# ReWireShield.net
KiCad netlist of a schematic drawn in EAGLE
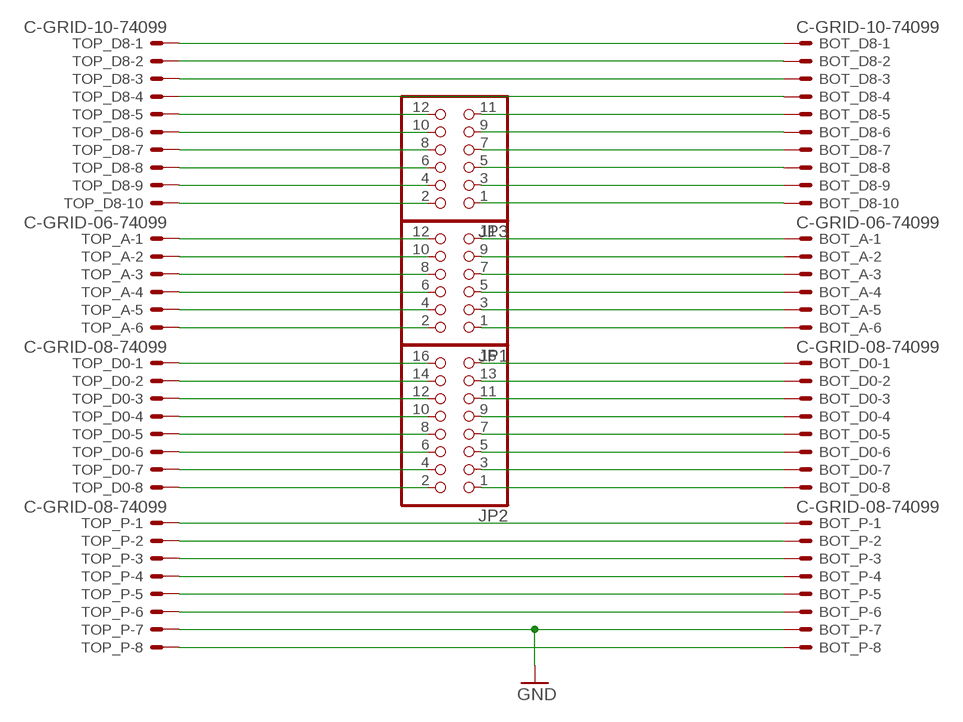
[diagram p0: schematic, sheet 1]

(export (version "E")
  (design (tool "Eeschema 10.0.6"))
  (components
    (comp (ref "BOT_A")
      (value "C-GRID-06-74099")
      (footprint "eagle-import:74099-06")
      (libsource (lib "eagle-import") (part "C-GRID-06-74099"))
    )
    (comp (ref "BOT_D0")
      (value "C-GRID-08-74099")
      (footprint "eagle-import:74099-08")
      (libsource (lib "eagle-import") (part "C-GRID-08-74099"))
    )
    (comp (ref "BOT_D8")
      (value "C-GRID-10-74099")
      (footprint "eagle-import:74099-10")
      (libsource (lib "eagle-import") (part "C-GRID-10-74099"))
    )
    (comp (ref "BOT_P")
      (value "C-GRID-08-74099")
      (footprint "eagle-import:74099-08")
      (libsource (lib "eagle-import") (part "C-GRID-08-74099"))
    )
    (comp (ref "JP1")
      (value "PINHD-2X6/90")
      (footprint "eagle-import:2X06_90")
      (libsource (lib "eagle-import") (part "PINHD-2X6/90"))
    )
    (comp (ref "JP2")
      (value "PINHD-2X8/90")
      (footprint "eagle-import:2X08_90")
      (libsource (lib "eagle-import") (part "PINHD-2X8/90"))
    )
    (comp (ref "JP3")
      (value "PINHD-2X6/90")
      (footprint "eagle-import:2X06_90")
      (libsource (lib "eagle-import") (part "PINHD-2X6/90"))
    )
    (comp (ref "TOP_A")
      (value "C-GRID-06-74099")
      (footprint "eagle-import:74099-06")
      (libsource (lib "eagle-import") (part "C-GRID-06-74099"))
    )
    (comp (ref "TOP_D0")
      (value "C-GRID-08-74099")
      (footprint "eagle-import:74099-08")
      (libsource (lib "eagle-import") (part "C-GRID-08-74099"))
    )
    (comp (ref "TOP_D8")
      (value "C-GRID-10-74099")
      (footprint "eagle-import:74099-10")
      (libsource (lib "eagle-import") (part "C-GRID-10-74099"))
    )
    (comp (ref "TOP_P")
      (value "C-GRID-08-74099")
      (footprint "eagle-import:74099-08")
      (libsource (lib "eagle-import") (part "C-GRID-08-74099"))
    )
  )
  (nets
    (net (code "1") (name "GND") (class "Default")
      (node (ref "BOT_P") (pin "7") (pinfunction "S_7") (pintype "passive"))
      (node (ref "TOP_P") (pin "7") (pinfunction "S_7") (pintype "passive"))
    )
    (net (code "2") (name "Net-(BOT_AA-S)") (class "Default")
      (node (ref "BOT_A") (pin "1") (pinfunction "S_1") (pintype "passive"))
      (node (ref "JP1") (pin "11") (pinfunction "11_11") (pintype "passive"))
    )
    (net (code "3") (name "Net-(BOT_AB-S)") (class "Default")
      (node (ref "BOT_A") (pin "2") (pinfunction "S_2") (pintype "passive"))
      (node (ref "JP1") (pin "9") (pinfunction "9_9") (pintype "passive"))
    )
    (net (code "4") (name "Net-(BOT_AC-S)") (class "Default")
      (node (ref "BOT_A") (pin "3") (pinfunction "S_3") (pintype "passive"))
      (node (ref "JP1") (pin "7") (pinfunction "7_7") (pintype "passive"))
    )
    (net (code "5") (name "Net-(BOT_AD-S)") (class "Default")
      (node (ref "BOT_A") (pin "4") (pinfunction "S_4") (pintype "passive"))
      (node (ref "JP1") (pin "5") (pinfunction "5_5") (pintype "passive"))
    )
    (net (code "6") (name "Net-(BOT_AE-S)") (class "Default")
      (node (ref "BOT_A") (pin "5") (pinfunction "S_5") (pintype "passive"))
      (node (ref "JP1") (pin "3") (pinfunction "3_3") (pintype "passive"))
    )
    (net (code "7") (name "Net-(BOT_AF-S)") (class "Default")
      (node (ref "BOT_A") (pin "6") (pinfunction "S_6") (pintype "passive"))
      (node (ref "JP1") (pin "1") (pinfunction "1_1") (pintype "passive"))
    )
    (net (code "8") (name "Net-(BOT_D0A-S)") (class "Default")
      (node (ref "BOT_D0") (pin "1") (pinfunction "S_1") (pintype "passive"))
      (node (ref "JP2") (pin "15") (pinfunction "15_15") (pintype "passive"))
    )
    (net (code "9") (name "Net-(BOT_D0B-S)") (class "Default")
      (node (ref "BOT_D0") (pin "2") (pinfunction "S_2") (pintype "passive"))
      (node (ref "JP2") (pin "13") (pinfunction "13_13") (pintype "passive"))
    )
    (net (code "10") (name "Net-(BOT_D0C-S)") (class "Default")
      (node (ref "BOT_D0") (pin "3") (pinfunction "S_3") (pintype "passive"))
      (node (ref "JP2") (pin "11") (pinfunction "11_11") (pintype "passive"))
    )
    (net (code "11") (name "Net-(BOT_D0D-S)") (class "Default")
      (node (ref "BOT_D0") (pin "4") (pinfunction "S_4") (pintype "passive"))
      (node (ref "JP2") (pin "9") (pinfunction "9_9") (pintype "passive"))
    )
    (net (code "12") (name "Net-(BOT_D0E-S)") (class "Default")
      (node (ref "BOT_D0") (pin "5") (pinfunction "S_5") (pintype "passive"))
      (node (ref "JP2") (pin "7") (pinfunction "7_7") (pintype "passive"))
    )
    (net (code "13") (name "Net-(BOT_D0F-S)") (class "Default")
      (node (ref "BOT_D0") (pin "6") (pinfunction "S_6") (pintype "passive"))
      (node (ref "JP2") (pin "5") (pinfunction "5_5") (pintype "passive"))
    )
    (net (code "14") (name "Net-(BOT_D0G-S)") (class "Default")
      (node (ref "BOT_D0") (pin "7") (pinfunction "S_7") (pintype "passive"))
      (node (ref "JP2") (pin "3") (pinfunction "3_3") (pintype "passive"))
    )
    (net (code "15") (name "Net-(BOT_D0H-S)") (class "Default")
      (node (ref "BOT_D0") (pin "8") (pinfunction "S_8") (pintype "passive"))
      (node (ref "JP2") (pin "1") (pinfunction "1_1") (pintype "passive"))
    )
    (net (code "16") (name "Net-(BOT_D8A-S)") (class "Default")
      (node (ref "BOT_D8") (pin "1") (pinfunction "S_1") (pintype "passive"))
      (node (ref "TOP_D8") (pin "1") (pinfunction "S_1") (pintype "passive"))
    )
    (net (code "17") (name "Net-(BOT_D8B-S)") (class "Default")
      (node (ref "BOT_D8") (pin "10") (pinfunction "S_10") (pintype "passive"))
      (node (ref "JP3") (pin "1") (pinfunction "1_1") (pintype "passive"))
    )
    (net (code "18") (name "Net-(BOT_D8C-S)") (class "Default")
      (node (ref "BOT_D8") (pin "2") (pinfunction "S_2") (pintype "passive"))
      (node (ref "TOP_D8") (pin "2") (pinfunction "S_2") (pintype "passive"))
    )
    (net (code "19") (name "Net-(BOT_D8D-S)") (class "Default")
      (node (ref "BOT_D8") (pin "3") (pinfunction "S_3") (pintype "passive"))
      (node (ref "TOP_D8") (pin "3") (pinfunction "S_3") (pintype "passive"))
    )
    (net (code "20") (name "Net-(BOT_D8E-S)") (class "Default")
      (node (ref "BOT_D8") (pin "4") (pinfunction "S_4") (pintype "passive"))
      (node (ref "TOP_D8") (pin "4") (pinfunction "S_4") (pintype "passive"))
    )
    (net (code "21") (name "Net-(BOT_D8F-S)") (class "Default")
      (node (ref "BOT_D8") (pin "5") (pinfunction "S_5") (pintype "passive"))
      (node (ref "JP3") (pin "11") (pinfunction "11_11") (pintype "passive"))
    )
    (net (code "22") (name "Net-(BOT_D8G-S)") (class "Default")
      (node (ref "BOT_D8") (pin "6") (pinfunction "S_6") (pintype "passive"))
      (node (ref "JP3") (pin "9") (pinfunction "9_9") (pintype "passive"))
    )
    (net (code "23") (name "Net-(BOT_D8H-S)") (class "Default")
      (node (ref "BOT_D8") (pin "7") (pinfunction "S_7") (pintype "passive"))
      (node (ref "JP3") (pin "7") (pinfunction "7_7") (pintype "passive"))
    )
    (net (code "24") (name "Net-(BOT_D8I-S)") (class "Default")
      (node (ref "BOT_D8") (pin "8") (pinfunction "S_8") (pintype "passive"))
      (node (ref "JP3") (pin "5") (pinfunction "5_5") (pintype "passive"))
    )
    (net (code "25") (name "Net-(BOT_D8J-S)") (class "Default")
      (node (ref "BOT_D8") (pin "9") (pinfunction "S_9") (pintype "passive"))
      (node (ref "JP3") (pin "3") (pinfunction "3_3") (pintype "passive"))
    )
    (net (code "26") (name "Net-(BOT_PA-S)") (class "Default")
      (node (ref "BOT_P") (pin "1") (pinfunction "S_1") (pintype "passive"))
      (node (ref "TOP_P") (pin "1") (pinfunction "S_1") (pintype "passive"))
    )
    (net (code "27") (name "Net-(BOT_PB-S)") (class "Default")
      (node (ref "BOT_P") (pin "2") (pinfunction "S_2") (pintype "passive"))
      (node (ref "TOP_P") (pin "2") (pinfunction "S_2") (pintype "passive"))
    )
    (net (code "28") (name "Net-(BOT_PC-S)") (class "Default")
      (node (ref "BOT_P") (pin "3") (pinfunction "S_3") (pintype "passive"))
      (node (ref "TOP_P") (pin "3") (pinfunction "S_3") (pintype "passive"))
    )
    (net (code "29") (name "Net-(BOT_PD-S)") (class "Default")
      (node (ref "BOT_P") (pin "4") (pinfunction "S_4") (pintype "passive"))
      (node (ref "TOP_P") (pin "4") (pinfunction "S_4") (pintype "passive"))
    )
    (net (code "30") (name "Net-(BOT_PE-S)") (class "Default")
      (node (ref "BOT_P") (pin "5") (pinfunction "S_5") (pintype "passive"))
      (node (ref "TOP_P") (pin "5") (pinfunction "S_5") (pintype "passive"))
    )
    (net (code "31") (name "Net-(BOT_PF-S)") (class "Default")
      (node (ref "BOT_P") (pin "6") (pinfunction "S_6") (pintype "passive"))
      (node (ref "TOP_P") (pin "6") (pinfunction "S_6") (pintype "passive"))
    )
    (net (code "32") (name "Net-(BOT_PH-S)") (class "Default")
      (node (ref "BOT_P") (pin "8") (pinfunction "S_8") (pintype "passive"))
      (node (ref "TOP_P") (pin "8") (pinfunction "S_8") (pintype "passive"))
    )
    (net (code "33") (name "Net-(TOP_AA-S)") (class "Default")
      (node (ref "JP1") (pin "12") (pinfunction "12_12") (pintype "passive"))
      (node (ref "TOP_A") (pin "1") (pinfunction "S_1") (pintype "passive"))
    )
    (net (code "34") (name "Net-(TOP_AB-S)") (class "Default")
      (node (ref "JP1") (pin "10") (pinfunction "10_10") (pintype "passive"))
      (node (ref "TOP_A") (pin "2") (pinfunction "S_2") (pintype "passive"))
    )
    (net (code "35") (name "Net-(TOP_AC-S)") (class "Default")
      (node (ref "JP1") (pin "8") (pinfunction "8_8") (pintype "passive"))
      (node (ref "TOP_A") (pin "3") (pinfunction "S_3") (pintype "passive"))
    )
    (net (code "36") (name "Net-(TOP_AD-S)") (class "Default")
      (node (ref "JP1") (pin "6") (pinfunction "6_6") (pintype "passive"))
      (node (ref "TOP_A") (pin "4") (pinfunction "S_4") (pintype "passive"))
    )
    (net (code "37") (name "Net-(TOP_AE-S)") (class "Default")
      (node (ref "JP1") (pin "4") (pinfunction "4_4") (pintype "passive"))
      (node (ref "TOP_A") (pin "5") (pinfunction "S_5") (pintype "passive"))
    )
    (net (code "38") (name "Net-(TOP_AF-S)") (class "Default")
      (node (ref "JP1") (pin "2") (pinfunction "2_2") (pintype "passive"))
      (node (ref "TOP_A") (pin "6") (pinfunction "S_6") (pintype "passive"))
    )
    (net (code "39") (name "Net-(TOP_D0A-S)") (class "Default")
      (node (ref "JP2") (pin "16") (pinfunction "16_16") (pintype "passive"))
      (node (ref "TOP_D0") (pin "1") (pinfunction "S_1") (pintype "passive"))
    )
    (net (code "40") (name "Net-(TOP_D0B-S)") (class "Default")
      (node (ref "JP2") (pin "14") (pinfunction "14_14") (pintype "passive"))
      (node (ref "TOP_D0") (pin "2") (pinfunction "S_2") (pintype "passive"))
    )
    (net (code "41") (name "Net-(TOP_D0C-S)") (class "Default")
      (node (ref "JP2") (pin "12") (pinfunction "12_12") (pintype "passive"))
      (node (ref "TOP_D0") (pin "3") (pinfunction "S_3") (pintype "passive"))
    )
    (net (code "42") (name "Net-(TOP_D0D-S)") (class "Default")
      (node (ref "JP2") (pin "10") (pinfunction "10_10") (pintype "passive"))
      (node (ref "TOP_D0") (pin "4") (pinfunction "S_4") (pintype "passive"))
    )
    (net (code "43") (name "Net-(TOP_D0E-S)") (class "Default")
      (node (ref "JP2") (pin "8") (pinfunction "8_8") (pintype "passive"))
      (node (ref "TOP_D0") (pin "5") (pinfunction "S_5") (pintype "passive"))
    )
    (net (code "44") (name "Net-(TOP_D0F-S)") (class "Default")
      (node (ref "JP2") (pin "6") (pinfunction "6_6") (pintype "passive"))
      (node (ref "TOP_D0") (pin "6") (pinfunction "S_6") (pintype "passive"))
    )
    (net (code "45") (name "Net-(TOP_D0G-S)") (class "Default")
      (node (ref "JP2") (pin "4") (pinfunction "4_4") (pintype "passive"))
      (node (ref "TOP_D0") (pin "7") (pinfunction "S_7") (pintype "passive"))
    )
    (net (code "46") (name "Net-(TOP_D0H-S)") (class "Default")
      (node (ref "JP2") (pin "2") (pinfunction "2_2") (pintype "passive"))
      (node (ref "TOP_D0") (pin "8") (pinfunction "S_8") (pintype "passive"))
    )
    (net (code "47") (name "Net-(TOP_D8B-S)") (class "Default")
      (node (ref "JP3") (pin "2") (pinfunction "2_2") (pintype "passive"))
      (node (ref "TOP_D8") (pin "10") (pinfunction "S_10") (pintype "passive"))
    )
    (net (code "48") (name "Net-(TOP_D8F-S)") (class "Default")
      (node (ref "JP3") (pin "12") (pinfunction "12_12") (pintype "passive"))
      (node (ref "TOP_D8") (pin "5") (pinfunction "S_5") (pintype "passive"))
    )
    (net (code "49") (name "Net-(TOP_D8G-S)") (class "Default")
      (node (ref "JP3") (pin "10") (pinfunction "10_10") (pintype "passive"))
      (node (ref "TOP_D8") (pin "6") (pinfunction "S_6") (pintype "passive"))
    )
    (net (code "50") (name "Net-(TOP_D8H-S)") (class "Default")
      (node (ref "JP3") (pin "8") (pinfunction "8_8") (pintype "passive"))
      (node (ref "TOP_D8") (pin "7") (pinfunction "S_7") (pintype "passive"))
    )
    (net (code "51") (name "Net-(TOP_D8I-S)") (class "Default")
      (node (ref "JP3") (pin "6") (pinfunction "6_6") (pintype "passive"))
      (node (ref "TOP_D8") (pin "8") (pinfunction "S_8") (pintype "passive"))
    )
    (net (code "52") (name "Net-(TOP_D8J-S)") (class "Default")
      (node (ref "JP3") (pin "4") (pinfunction "4_4") (pintype "passive"))
      (node (ref "TOP_D8") (pin "9") (pinfunction "S_9") (pintype "passive"))
    )
  )
)
